# HK0J2071758B03-AM-FPC.net
KiCad netlist of a schematic drawn in Altium Designer
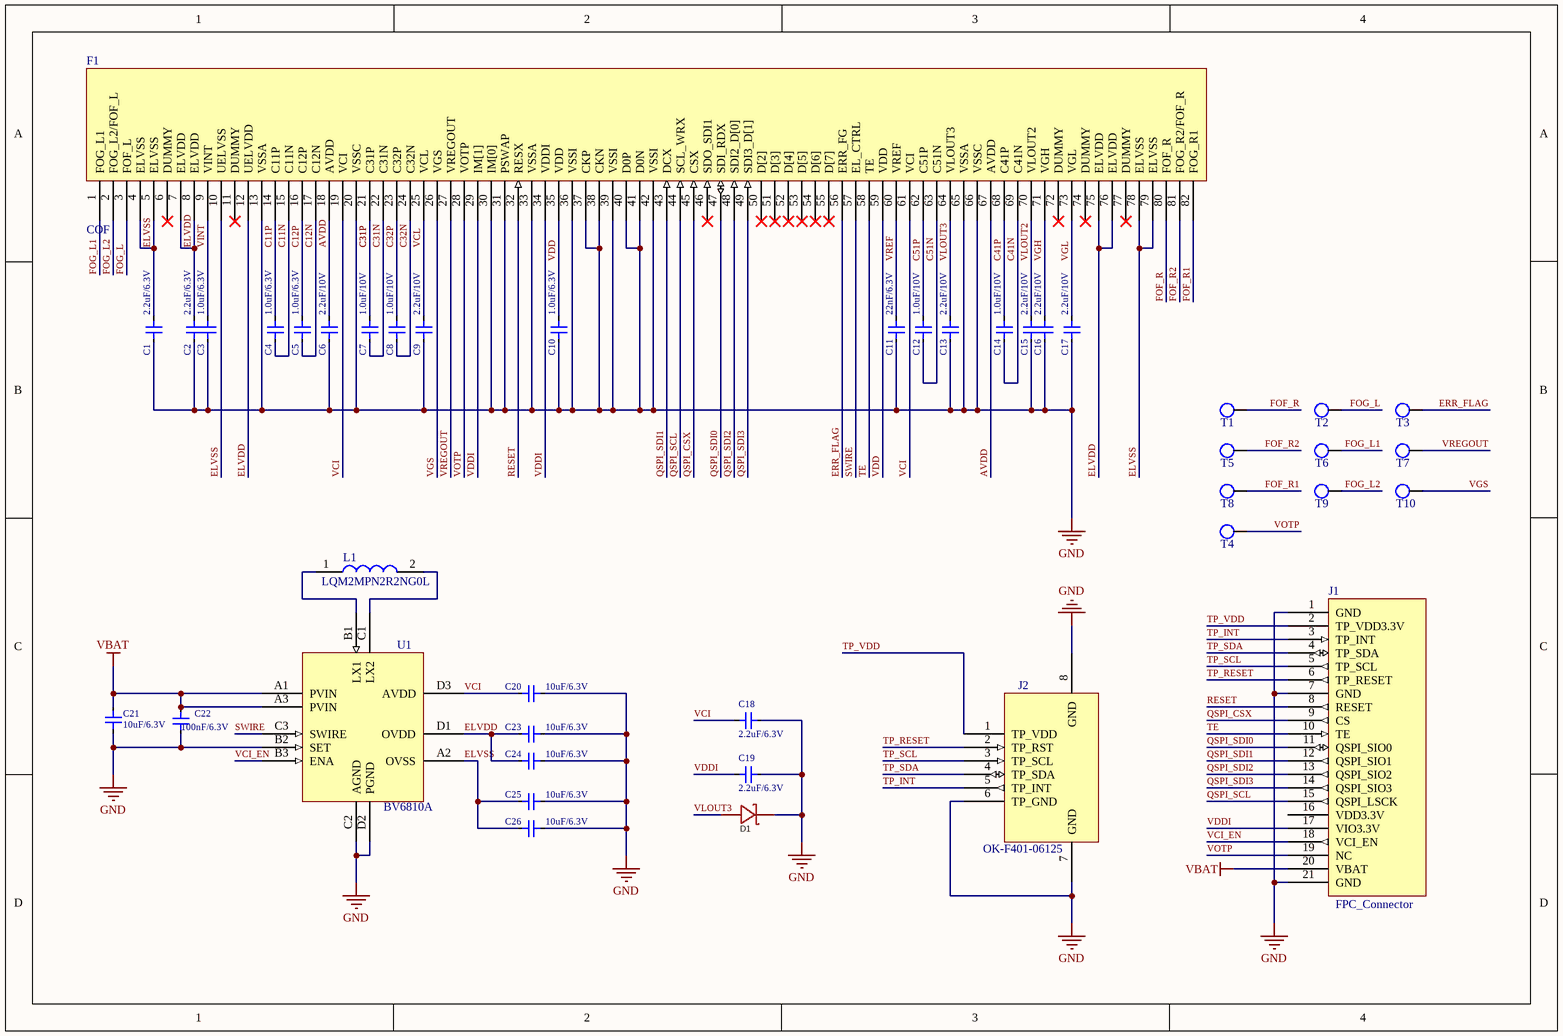
[diagram p0: HK0J2071758B03-AM-FPC.SchDoc]

(export (version "E")
  (design (tool "Eeschema 10.0.6"))
  (components
    (comp (ref "C1")
      (value "2.2uF/6.3V")
      (footprint "CAPC0603X33N")
      (description "NONE")
      (fields
        (field (name "MANUFACTURER") "Murata")
        (field (name "MANUFACTURER PART NUMBER") "GRM033R61A105ME15D")
      )
      (libsource (lib "COF") (part "Capacitor"))
    )
    (comp (ref "C2")
      (value "2.2uF/6.3V")
      (footprint "CAPC0603X33N")
      (description "NONE")
      (fields
        (field (name "MANUFACTURER") "Murata")
        (field (name "MANUFACTURER PART NUMBER") "GRM033R61A105ME15D")
      )
      (libsource (lib "COF") (part "Capacitor"))
    )
    (comp (ref "C3")
      (value "1.0uF/6.3V")
      (footprint "CAPC0603X33N")
      (description "NONE")
      (fields
        (field (name "MANUFACTURER") "Murata")
        (field (name "MANUFACTURER PART NUMBER") "GRM033R61A105ME15D")
      )
      (libsource (lib "COF") (part "Capacitor"))
    )
    (comp (ref "C4")
      (value "1.0uF/6.3V")
      (footprint "CAPC0603X33N")
      (description "NONE")
      (fields
        (field (name "MANUFACTURER") "Murata")
        (field (name "MANUFACTURER PART NUMBER") "GRM033R61A105ME15D")
      )
      (libsource (lib "COF") (part "Capacitor"))
    )
    (comp (ref "C5")
      (value "1.0uF/6.3V")
      (footprint "CAPC0603X33N")
      (description "NONE")
      (fields
        (field (name "MANUFACTURER") "Murata")
        (field (name "MANUFACTURER PART NUMBER") "GRM033R61A105ME15D")
      )
      (libsource (lib "COF") (part "Capacitor"))
    )
    (comp (ref "C6")
      (value "2.2uF/10V")
      (footprint "CAPC0603X33N")
      (description "NONE")
      (fields
        (field (name "MANUFACTURER") "Murata")
        (field (name "MANUFACTURER PART NUMBER") "GRM033R61A105ME15D")
      )
      (libsource (lib "COF") (part "Capacitor"))
    )
    (comp (ref "C7")
      (value "1.0uF/10V")
      (footprint "CAPC0603X33N")
      (description "NONE")
      (fields
        (field (name "MANUFACTURER") "Murata")
        (field (name "MANUFACTURER PART NUMBER") "GRM033R61A105ME15D")
      )
      (libsource (lib "COF") (part "Capacitor"))
    )
    (comp (ref "C8")
      (value "1.0uF/10V")
      (footprint "CAPC0603X33N")
      (description "NONE")
      (fields
        (field (name "MANUFACTURER") "Murata")
        (field (name "MANUFACTURER PART NUMBER") "GRM033R61A105ME15D")
      )
      (libsource (lib "COF") (part "Capacitor"))
    )
    (comp (ref "C9")
      (value "2.2uF/10V")
      (footprint "CAPC0603X33N")
      (description "NONE")
      (fields
        (field (name "MANUFACTURER") "Murata")
        (field (name "MANUFACTURER PART NUMBER") "GRM033R61A105ME15D")
      )
      (libsource (lib "COF") (part "Capacitor"))
    )
    (comp (ref "C10")
      (value "1.0uF/6.3V")
      (footprint "CAPC0603X33N")
      (description "NONE")
      (fields
        (field (name "MANUFACTURER") "Murata")
        (field (name "MANUFACTURER PART NUMBER") "GRM033R61A105ME15D")
      )
      (libsource (lib "COF") (part "Capacitor"))
    )
    (comp (ref "C11")
      (value "22nF/6.3V")
      (footprint "CAPC0603X33N")
      (description "NONE")
      (fields
        (field (name "MANUFACTURER") "Murata")
        (field (name "MANUFACTURER PART NUMBER") "GRM033R61A105ME15D")
      )
      (libsource (lib "COF") (part "Capacitor"))
    )
    (comp (ref "C12")
      (value "1.0uF/10V")
      (footprint "CAPC0603X33N")
      (description "NONE")
      (fields
        (field (name "MANUFACTURER") "Murata")
        (field (name "MANUFACTURER PART NUMBER") "GRM033R61A105ME15D")
      )
      (libsource (lib "COF") (part "Capacitor"))
    )
    (comp (ref "C13")
      (value "2.2uF/10V")
      (footprint "CAPC0603X33N")
      (description "NONE")
      (fields
        (field (name "MANUFACTURER") "Murata")
        (field (name "MANUFACTURER PART NUMBER") "GRM033R61A105ME15D")
      )
      (libsource (lib "COF") (part "Capacitor"))
    )
    (comp (ref "C14")
      (value "1.0uF/10V")
      (footprint "CAPC0603X33N")
      (description "NONE")
      (fields
        (field (name "MANUFACTURER") "Murata")
        (field (name "MANUFACTURER PART NUMBER") "GRM033R61A105ME15D")
      )
      (libsource (lib "COF") (part "Capacitor"))
    )
    (comp (ref "C15")
      (value "2.2uF/10V")
      (footprint "CAPC0603X33N")
      (description "NONE")
      (fields
        (field (name "MANUFACTURER") "Murata")
        (field (name "MANUFACTURER PART NUMBER") "GRM033R61A105ME15D")
      )
      (libsource (lib "COF") (part "Capacitor"))
    )
    (comp (ref "C16")
      (value "2.2uF/10V")
      (footprint "CAPC0603X33N")
      (description "NONE")
      (fields
        (field (name "MANUFACTURER") "Murata")
        (field (name "MANUFACTURER PART NUMBER") "GRM033R61A105ME15D")
      )
      (libsource (lib "COF") (part "Capacitor"))
    )
    (comp (ref "C17")
      (value "2.2uF/10V")
      (footprint "CAPC0603X33N")
      (description "NONE")
      (fields
        (field (name "MANUFACTURER") "Murata")
        (field (name "MANUFACTURER PART NUMBER") "GRM033R61A105ME15D")
      )
      (libsource (lib "COF") (part "Capacitor"))
    )
    (comp (ref "C18")
      (value "2.2uF/6.3V")
      (footprint "CAPC0603X33N")
      (description "NONE")
      (fields
        (field (name "MANUFACTURER") "Murata")
        (field (name "MANUFACTURER PART NUMBER") "GRM033R61A105ME15D")
      )
      (libsource (lib "COF") (part "Capacitor"))
    )
    (comp (ref "C19")
      (value "2.2uF/6.3V")
      (footprint "CAPC0603X33N")
      (description "NONE")
      (fields
        (field (name "MANUFACTURER") "Murata")
        (field (name "MANUFACTURER PART NUMBER") "GRM033R61A105ME15D")
      )
      (libsource (lib "COF") (part "Capacitor"))
    )
    (comp (ref "C20")
      (value "10uF/6.3V")
      (footprint "CAPC1005X57N")
      (description "NONE")
      (fields
        (field (name "MANUFACTURER") "Murata")
        (field (name "MANUFACTURER PART NUMBER") "GRM033R61A105ME15D")
      )
      (libsource (lib "COF") (part "Capacitor"))
    )
    (comp (ref "C21")
      (value "10uF/6.3V")
      (footprint "CAPC1005X57N")
      (description "NONE")
      (fields
        (field (name "MANUFACTURER") "Murata")
        (field (name "MANUFACTURER PART NUMBER") "GRM033R61A105ME15D")
      )
      (libsource (lib "COF") (part "Capacitor"))
    )
    (comp (ref "C22")
      (value "100nF/6.3V")
      (footprint "CAPC0603X33N")
      (description "NONE")
      (fields
        (field (name "MANUFACTURER") "Murata")
        (field (name "MANUFACTURER PART NUMBER") "GRM033R61A105ME15D")
      )
      (libsource (lib "COF") (part "Capacitor"))
    )
    (comp (ref "C23")
      (value "10uF/6.3V")
      (footprint "CAPC1005X57N")
      (description "NONE")
      (fields
        (field (name "MANUFACTURER") "Murata")
        (field (name "MANUFACTURER PART NUMBER") "GRM033R61A105ME15D")
      )
      (libsource (lib "COF") (part "Capacitor"))
    )
    (comp (ref "C24")
      (value "10uF/6.3V")
      (footprint "CAPC1005X57N")
      (description "NONE")
      (fields
        (field (name "MANUFACTURER") "Murata")
        (field (name "MANUFACTURER PART NUMBER") "GRM033R61A105ME15D")
      )
      (libsource (lib "COF") (part "Capacitor"))
    )
    (comp (ref "C25")
      (value "10uF/6.3V")
      (footprint "CAPC1005X57N")
      (description "NONE")
      (fields
        (field (name "MANUFACTURER") "Murata")
        (field (name "MANUFACTURER PART NUMBER") "GRM033R61A105ME15D")
      )
      (libsource (lib "COF") (part "Capacitor"))
    )
    (comp (ref "C26")
      (value "10uF/6.3V")
      (footprint "CAPC1005X57N")
      (description "NONE")
      (fields
        (field (name "MANUFACTURER") "Murata")
        (field (name "MANUFACTURER PART NUMBER") "GRM033R61A105ME15D")
      )
      (libsource (lib "COF") (part "Capacitor"))
    )
    (comp (ref "D1")
      (value "LDSR01S30ST5G")
      (footprint "DFN0603-D_L0.6-W0.3-P0.34-RD")
      (fields (field (name "MANUFACTURER") "LRC(乐山无线电)"))
      (libsource (lib "COF") (part "LDSR01S30ST5G"))
    )
    (comp (ref "F1") (value "COF") (footprint "COF Connector") (libsource (lib "COF") (part "COF")))
    (comp (ref "J1")
      (value "FPC_Connector")
      (footprint "FPC Connector")
      (libsource (lib "COF") (part "21Pin_Connector"))
    )
    (comp (ref "J2")
      (value "OK-F401-06125")
      (footprint "FFC-SMD_6P-P0.50_FH34SRJ-6S-0.5SH")
      (libsource (lib "COF") (part "OK-F401-06125"))
    )
    (comp (ref "L1")
      (value "LQM2MPN2R2NG0L")
      (footprint "LQM2MPN1R0NG0L")
      (description "Inductor")
      (fields (field (name "MOUSER PART NUMBER") "81-LQM2MPN2R2NG0L"))
      (libsource (lib "COF") (part "LQM2MPN2R2NG0L"))
    )
    (comp (ref "T1")
      (value "Test_Point")
      (footprint "TP-C045-PI")
      (libsource (lib "COF") (part "Test_Point"))
    )
    (comp (ref "T2")
      (value "Test_Point")
      (footprint "TP-C045-PI")
      (libsource (lib "COF") (part "Test_Point"))
    )
    (comp (ref "T3")
      (value "Test_Point")
      (footprint "TP-C045-PI")
      (libsource (lib "COF") (part "Test_Point"))
    )
    (comp (ref "T4")
      (value "Test_Point")
      (footprint "TP-C045-PI")
      (libsource (lib "COF") (part "Test_Point"))
    )
    (comp (ref "T5")
      (value "Test_Point")
      (footprint "TP-C045-PI")
      (libsource (lib "COF") (part "Test_Point"))
    )
    (comp (ref "T6")
      (value "Test_Point")
      (footprint "TP-C045-PI")
      (libsource (lib "COF") (part "Test_Point"))
    )
    (comp (ref "T7")
      (value "Test_Point")
      (footprint "TP-C045-PI")
      (libsource (lib "COF") (part "Test_Point"))
    )
    (comp (ref "T8")
      (value "Test_Point")
      (footprint "TP-C045-PI")
      (libsource (lib "COF") (part "Test_Point"))
    )
    (comp (ref "T9")
      (value "Test_Point")
      (footprint "TP-C045-PI")
      (libsource (lib "COF") (part "Test_Point"))
    )
    (comp (ref "T10")
      (value "Test_Point")
      (footprint "TP-C045-PI")
      (libsource (lib "COF") (part "Test_Point"))
    )
    (comp (ref "U1")
      (value "BV6810A")
      (footprint "WLCSP-12_L1.7-W1.5-R4-C3-P0.40-TL-1")
      (libsource (lib "COF") (part "BV6810A"))
    )
  )
  (nets
    (net (code "1") (name "/AVDD") (class "Default")
      (node (ref "C6") (pin "1") (pinfunction "1_1") (pintype "passive"))
      (node (ref "F1") (pin "18") (pinfunction "AVDD_18") (pintype "power_in"))
      (node (ref "F1") (pin "67") (pinfunction "AVDD_67") (pintype "power_in"))
    )
    (net (code "2") (name "/C11N") (class "Default")
      (node (ref "C4") (pin "2") (pinfunction "2_2") (pintype "passive"))
      (node (ref "F1") (pin "15") (pinfunction "C11N_15") (pintype "tri_state"))
    )
    (net (code "3") (name "/C11P") (class "Default")
      (node (ref "C4") (pin "1") (pinfunction "1_1") (pintype "passive"))
      (node (ref "F1") (pin "14") (pinfunction "C11P_14") (pintype "tri_state"))
    )
    (net (code "4") (name "/C12N") (class "Default")
      (node (ref "C5") (pin "2") (pinfunction "2_2") (pintype "passive"))
      (node (ref "F1") (pin "17") (pinfunction "C12N_17") (pintype "tri_state"))
    )
    (net (code "5") (name "/C12P") (class "Default")
      (node (ref "C5") (pin "1") (pinfunction "1_1") (pintype "passive"))
      (node (ref "F1") (pin "16") (pinfunction "C12P_16") (pintype "tri_state"))
    )
    (net (code "6") (name "/C31N") (class "Default")
      (node (ref "C7") (pin "2") (pinfunction "2_2") (pintype "passive"))
      (node (ref "F1") (pin "22") (pinfunction "C31N_22") (pintype "tri_state"))
    )
    (net (code "7") (name "/C31P") (class "Default")
      (node (ref "C7") (pin "1") (pinfunction "1_1") (pintype "passive"))
      (node (ref "F1") (pin "21") (pinfunction "C31P_21") (pintype "tri_state"))
    )
    (net (code "8") (name "/C32N") (class "Default")
      (node (ref "C8") (pin "2") (pinfunction "2_2") (pintype "passive"))
      (node (ref "F1") (pin "24") (pinfunction "C32N_24") (pintype "tri_state"))
    )
    (net (code "9") (name "/C32P") (class "Default")
      (node (ref "C8") (pin "1") (pinfunction "1_1") (pintype "passive"))
      (node (ref "F1") (pin "23") (pinfunction "C32P_23") (pintype "tri_state"))
    )
    (net (code "10") (name "/C41N") (class "Default")
      (node (ref "C14") (pin "2") (pinfunction "2_2") (pintype "passive"))
      (node (ref "F1") (pin "69") (pinfunction "C41N_69") (pintype "tri_state"))
    )
    (net (code "11") (name "/C41P") (class "Default")
      (node (ref "C14") (pin "1") (pinfunction "1_1") (pintype "passive"))
      (node (ref "F1") (pin "68") (pinfunction "C41P_68") (pintype "tri_state"))
    )
    (net (code "12") (name "/C51N") (class "Default")
      (node (ref "C12") (pin "2") (pinfunction "2_2") (pintype "passive"))
      (node (ref "F1") (pin "63") (pinfunction "C51N_63") (pintype "tri_state"))
    )
    (net (code "13") (name "/C51P") (class "Default")
      (node (ref "C12") (pin "1") (pinfunction "1_1") (pintype "passive"))
      (node (ref "F1") (pin "62") (pinfunction "C51P_62") (pintype "tri_state"))
    )
    (net (code "14") (name "/ELVDD") (class "Default")
      (node (ref "C2") (pin "1") (pinfunction "1_1") (pintype "passive"))
      (node (ref "C23") (pin "2") (pinfunction "2_2") (pintype "passive"))
      (node (ref "C24") (pin "2") (pinfunction "2_2") (pintype "passive"))
      (node (ref "F1") (pin "12") (pinfunction "UELVDD_12") (pintype "power_in"))
      (node (ref "F1") (pin "7") (pinfunction "ELVDD_7") (pintype "power_in"))
      (node (ref "F1") (pin "75") (pinfunction "ELVDD_75") (pintype "power_in"))
      (node (ref "F1") (pin "76") (pinfunction "ELVDD_76") (pintype "power_in"))
      (node (ref "F1") (pin "8") (pinfunction "ELVDD_8") (pintype "power_in"))
      (node (ref "U1") (pin "D1") (pinfunction "OVDD_D1") (pintype "power_in"))
    )
    (net (code "15") (name "/ELVSS") (class "Default")
      (node (ref "C1") (pin "1") (pinfunction "1_1") (pintype "passive"))
      (node (ref "C25") (pin "2") (pinfunction "2_2") (pintype "passive"))
      (node (ref "C26") (pin "2") (pinfunction "2_2") (pintype "passive"))
      (node (ref "F1") (pin "10") (pinfunction "UELVSS_10") (pintype "power_in"))
      (node (ref "F1") (pin "4") (pinfunction "ELVSS_4") (pintype "power_in"))
      (node (ref "F1") (pin "5") (pinfunction "ELVSS_5") (pintype "power_in"))
      (node (ref "F1") (pin "78") (pinfunction "ELVSS_78") (pintype "power_in"))
      (node (ref "F1") (pin "79") (pinfunction "ELVSS_79") (pintype "power_in"))
      (node (ref "U1") (pin "A2") (pinfunction "OVSS_A2") (pintype "power_in"))
    )
    (net (code "16") (name "/ERR_FLAG") (class "Default")
      (node (ref "F1") (pin "56") (pinfunction "ERR_FG_56") (pintype "tri_state"))
      (node (ref "T3") (pin "1") (pinfunction "1_1") (pintype "passive"))
    )
    (net (code "17") (name "/FOF_R") (class "Default")
      (node (ref "F1") (pin "80") (pinfunction "FOF_R_80") (pintype "tri_state"))
      (node (ref "T1") (pin "1") (pinfunction "1_1") (pintype "passive"))
    )
    (net (code "18") (name "/FOF_R1") (class "Default")
      (node (ref "F1") (pin "82") (pinfunction "FOG_R1_82") (pintype "tri_state"))
      (node (ref "T8") (pin "1") (pinfunction "1_1") (pintype "passive"))
    )
    (net (code "19") (name "/FOF_R2") (class "Default")
      (node (ref "F1") (pin "81") (pinfunction "FOG_R2/FOF_R_81") (pintype "tri_state"))
      (node (ref "T5") (pin "1") (pinfunction "1_1") (pintype "passive"))
    )
    (net (code "20") (name "/FOG_L") (class "Default")
      (node (ref "F1") (pin "3") (pinfunction "FOF_L_3") (pintype "tri_state"))
      (node (ref "T2") (pin "1") (pinfunction "1_1") (pintype "passive"))
    )
    (net (code "21") (name "/FOG_L1") (class "Default")
      (node (ref "F1") (pin "1") (pinfunction "FOG_L1_1") (pintype "tri_state"))
      (node (ref "T6") (pin "1") (pinfunction "1_1") (pintype "passive"))
    )
    (net (code "22") (name "/FOG_L2") (class "Default")
      (node (ref "F1") (pin "2") (pinfunction "FOG_L2/FOF_L_2") (pintype "tri_state"))
      (node (ref "T9") (pin "1") (pinfunction "1_1") (pintype "passive"))
    )
    (net (code "23") (name "/QSPI_CSX") (class "Default")
      (node (ref "F1") (pin "45") (pinfunction "CSX_45") (pintype "input"))
      (node (ref "J1") (pin "9") (pinfunction "CS_9") (pintype "output"))
    )
    (net (code "24") (name "/QSPI_SCL") (class "Default")
      (node (ref "F1") (pin "44") (pinfunction "SCL_WRX_44") (pintype "input"))
      (node (ref "J1") (pin "15") (pinfunction "QSPI_LSCK_15") (pintype "output"))
    )
    (net (code "25") (name "/QSPI_SDI0") (class "Default")
      (node (ref "F1") (pin "47") (pinfunction "SDI_RDX_47") (pintype "bidirectional"))
      (node (ref "J1") (pin "11") (pinfunction "QSPI_SIO0_11") (pintype "bidirectional"))
    )
    (net (code "26") (name "/QSPI_SDI1") (class "Default")
      (node (ref "F1") (pin "43") (pinfunction "DCX_43") (pintype "input"))
      (node (ref "J1") (pin "12") (pinfunction "QSPI_SIO1_12") (pintype "output"))
    )
    (net (code "27") (name "/QSPI_SDI2") (class "Default")
      (node (ref "F1") (pin "48") (pinfunction "SDI2_D[0]_48") (pintype "input"))
      (node (ref "J1") (pin "13") (pinfunction "QSPI_SIO2_13") (pintype "output"))
    )
    (net (code "28") (name "/QSPI_SDI3") (class "Default")
      (node (ref "F1") (pin "49") (pinfunction "SDI3_D[1]_49") (pintype "input"))
      (node (ref "J1") (pin "14") (pinfunction "QSPI_SIO3_14") (pintype "output"))
    )
    (net (code "29") (name "/RESET") (class "Default")
      (node (ref "F1") (pin "32") (pinfunction "RESX_32") (pintype "input"))
      (node (ref "J1") (pin "8") (pinfunction "RESET_8") (pintype "output"))
    )
    (net (code "30") (name "/SWIRE") (class "Default")
      (node (ref "F1") (pin "57") (pinfunction "EL_CTRL_57") (pintype "tri_state"))
      (node (ref "U1") (pin "C3") (pinfunction "SWIRE_C3") (pintype "input"))
    )
    (net (code "31") (name "/TE") (class "Default")
      (node (ref "F1") (pin "58") (pinfunction "TE_58") (pintype "tri_state"))
      (node (ref "J1") (pin "10") (pinfunction "TE_10") (pintype "input"))
    )
    (net (code "32") (name "/TP_INT") (class "Default")
      (node (ref "J1") (pin "3") (pinfunction "TP_INT_3") (pintype "input"))
      (node (ref "J2") (pin "5") (pinfunction "TP_INT_5") (pintype "output"))
    )
    (net (code "33") (name "/TP_RESET") (class "Default")
      (node (ref "J1") (pin "6") (pinfunction "TP_RESET_6") (pintype "output"))
      (node (ref "J2") (pin "2") (pinfunction "TP_RST_2") (pintype "input"))
    )
    (net (code "34") (name "/TP_SCL") (class "Default")
      (node (ref "J1") (pin "5") (pinfunction "TP_SCL_5") (pintype "output"))
      (node (ref "J2") (pin "3") (pinfunction "TP_SCL_3") (pintype "input"))
    )
    (net (code "35") (name "/TP_SDA") (class "Default")
      (node (ref "J1") (pin "4") (pinfunction "TP_SDA_4") (pintype "bidirectional"))
      (node (ref "J2") (pin "4") (pinfunction "TP_SDA_4") (pintype "bidirectional"))
    )
    (net (code "36") (name "/TP_VDD") (class "Default")
      (node (ref "J1") (pin "2") (pinfunction "TP_VDD3.3V_2") (pintype "power_in"))
      (node (ref "J2") (pin "1") (pinfunction "TP_VDD_1") (pintype "power_in"))
    )
    (net (code "37") (name "/VCI") (class "Default")
      (node (ref "C18") (pin "1") (pinfunction "1_1") (pintype "passive"))
      (node (ref "C20") (pin "2") (pinfunction "2_2") (pintype "passive"))
      (node (ref "F1") (pin "19") (pinfunction "VCI_19") (pintype "power_in"))
      (node (ref "F1") (pin "61") (pinfunction "VCI_61") (pintype "power_in"))
      (node (ref "U1") (pin "D3") (pinfunction "AVDD_D3") (pintype "power_in"))
    )
    (net (code "38") (name "/VCI_EN") (class "Default")
      (node (ref "J1") (pin "18") (pinfunction "VCI_EN_18") (pintype "output"))
      (node (ref "U1") (pin "B3") (pinfunction "ENA_B3") (pintype "input"))
    )
    (net (code "39") (name "/VCL") (class "Default")
      (node (ref "C9") (pin "1") (pinfunction "1_1") (pintype "passive"))
      (node (ref "F1") (pin "25") (pinfunction "VCL_25") (pintype "power_in"))
    )
    (net (code "40") (name "/VDD") (class "Default")
      (node (ref "C10") (pin "1") (pinfunction "1_1") (pintype "passive"))
      (node (ref "F1") (pin "35") (pinfunction "VDD_35") (pintype "power_in"))
      (node (ref "F1") (pin "59") (pinfunction "VDD_59") (pintype "power_in"))
    )
    (net (code "41") (name "/VDDI") (class "Default")
      (node (ref "C19") (pin "1") (pinfunction "1_1") (pintype "passive"))
      (node (ref "F1") (pin "29") (pinfunction "IM[1]_29") (pintype "passive"))
      (node (ref "F1") (pin "34") (pinfunction "VDDI_34") (pintype "power_in"))
      (node (ref "J1") (pin "17") (pinfunction "VIO3.3V_17") (pintype "power_in"))
    )
    (net (code "42") (name "/VGH") (class "Default")
      (node (ref "C16") (pin "1") (pinfunction "1_1") (pintype "passive"))
      (node (ref "F1") (pin "71") (pinfunction "VGH_71") (pintype "tri_state"))
    )
    (net (code "43") (name "/VGL") (class "Default")
      (node (ref "C17") (pin "1") (pinfunction "1_1") (pintype "passive"))
      (node (ref "F1") (pin "73") (pinfunction "VGL_73") (pintype "power_in"))
    )
    (net (code "44") (name "/VGS") (class "Default")
      (node (ref "F1") (pin "26") (pinfunction "VGS_26") (pintype "power_in"))
      (node (ref "T10") (pin "1") (pinfunction "1_1") (pintype "passive"))
    )
    (net (code "45") (name "/VINT") (class "Default")
      (node (ref "C3") (pin "1") (pinfunction "1_1") (pintype "passive"))
      (node (ref "F1") (pin "9") (pinfunction "VINT_9") (pintype "tri_state"))
    )
    (net (code "46") (name "/VLOUT2") (class "Default")
      (node (ref "C15") (pin "1") (pinfunction "1_1") (pintype "passive"))
      (node (ref "F1") (pin "70") (pinfunction "VLOUT2_70") (pintype "power_in"))
    )
    (net (code "47") (name "/VLOUT3") (class "Default")
      (node (ref "C13") (pin "1") (pinfunction "1_1") (pintype "passive"))
      (node (ref "D1") (pin "2") (pinfunction "A_2") (pintype "passive"))
      (node (ref "F1") (pin "64") (pinfunction "VLOUT3_64") (pintype "power_in"))
    )
    (net (code "48") (name "/VOTP") (class "Default")
      (node (ref "F1") (pin "28") (pinfunction "VOTP_28") (pintype "power_in"))
      (node (ref "J1") (pin "19") (pinfunction "NC_19") (pintype "passive"))
      (node (ref "T4") (pin "1") (pinfunction "1_1") (pintype "passive"))
    )
    (net (code "49") (name "/VREF") (class "Default")
      (node (ref "C11") (pin "1") (pinfunction "1_1") (pintype "passive"))
      (node (ref "F1") (pin "60") (pinfunction "VREF_60") (pintype "power_in"))
    )
    (net (code "50") (name "/VREGOUT") (class "Default")
      (node (ref "F1") (pin "27") (pinfunction "VREGOUT_27") (pintype "power_in"))
      (node (ref "T7") (pin "1") (pinfunction "1_1") (pintype "passive"))
    )
    (net (code "51") (name "GND") (class "Default")
      (node (ref "C1") (pin "2") (pinfunction "2_2") (pintype "passive"))
      (node (ref "C10") (pin "2") (pinfunction "2_2") (pintype "passive"))
      (node (ref "C11") (pin "2") (pinfunction "2_2") (pintype "passive"))
      (node (ref "C13") (pin "2") (pinfunction "2_2") (pintype "passive"))
      (node (ref "C15") (pin "2") (pinfunction "2_2") (pintype "passive"))
      (node (ref "C16") (pin "2") (pinfunction "2_2") (pintype "passive"))
      (node (ref "C17") (pin "2") (pinfunction "2_2") (pintype "passive"))
      (node (ref "C18") (pin "2") (pinfunction "2_2") (pintype "passive"))
      (node (ref "C19") (pin "2") (pinfunction "2_2") (pintype "passive"))
      (node (ref "C2") (pin "2") (pinfunction "2_2") (pintype "passive"))
      (node (ref "C20") (pin "1") (pinfunction "1_1") (pintype "passive"))
      (node (ref "C21") (pin "1") (pinfunction "1_1") (pintype "passive"))
      (node (ref "C22") (pin "2") (pinfunction "2_2") (pintype "passive"))
      (node (ref "C23") (pin "1") (pinfunction "1_1") (pintype "passive"))
      (node (ref "C24") (pin "1") (pinfunction "1_1") (pintype "passive"))
      (node (ref "C25") (pin "1") (pinfunction "1_1") (pintype "passive"))
      (node (ref "C26") (pin "1") (pinfunction "1_1") (pintype "passive"))
      (node (ref "C3") (pin "2") (pinfunction "2_2") (pintype "passive"))
      (node (ref "C6") (pin "2") (pinfunction "2_2") (pintype "passive"))
      (node (ref "C9") (pin "2") (pinfunction "2_2") (pintype "passive"))
      (node (ref "D1") (pin "1") (pinfunction "C_1") (pintype "passive"))
      (node (ref "F1") (pin "13") (pinfunction "VSSA_13") (pintype "power_in"))
      (node (ref "F1") (pin "20") (pinfunction "VSSC_20") (pintype "power_in"))
      (node (ref "F1") (pin "30") (pinfunction "IM[0]_30") (pintype "passive"))
      (node (ref "F1") (pin "31") (pinfunction "PSWAP_31") (pintype "passive"))
      (node (ref "F1") (pin "33") (pinfunction "VSSA_33") (pintype "power_in"))
      (node (ref "F1") (pin "36") (pinfunction "VSSI_36") (pintype "power_in"))
      (node (ref "F1") (pin "37") (pinfunction "CKP_37") (pintype "passive"))
      (node (ref "F1") (pin "38") (pinfunction "CKN_38") (pintype "passive"))
      (node (ref "F1") (pin "39") (pinfunction "VSSI_39") (pintype "power_in"))
      (node (ref "F1") (pin "40") (pinfunction "D0P_40") (pintype "passive"))
      (node (ref "F1") (pin "41") (pinfunction "D0N_41") (pintype "passive"))
      (node (ref "F1") (pin "42") (pinfunction "VSSI_42") (pintype "power_in"))
      (node (ref "F1") (pin "65") (pinfunction "VSSA_65") (pintype "power_in"))
      (node (ref "F1") (pin "66") (pinfunction "VSSC_66") (pintype "power_in"))
      (node (ref "J1") (pin "1") (pinfunction "GND_1") (pintype "power_in"))
      (node (ref "J1") (pin "21") (pinfunction "GND_21") (pintype "power_in"))
      (node (ref "J1") (pin "7") (pinfunction "GND_7") (pintype "power_in"))
      (node (ref "J2") (pin "6") (pinfunction "TP_GND_6") (pintype "power_in"))
      (node (ref "J2") (pin "7") (pinfunction "GND_7") (pintype "power_in"))
      (node (ref "J2") (pin "8") (pinfunction "GND_8") (pintype "power_in"))
      (node (ref "U1") (pin "B2") (pinfunction "SET_B2") (pintype "input"))
      (node (ref "U1") (pin "C2") (pinfunction "AGND_C2") (pintype "power_in"))
      (node (ref "U1") (pin "D2") (pinfunction "PGND_D2") (pintype "power_in"))
    )
    (net (code "52") (name "Net-(U1-LX1)") (class "Default")
      (node (ref "L1") (pin "1") (pinfunction "1_1") (pintype "passive"))
      (node (ref "U1") (pin "B1") (pinfunction "LX1_B1") (pintype "input"))
    )
    (net (code "53") (name "Net-(U1-LX2)") (class "Default")
      (node (ref "L1") (pin "2") (pinfunction "2_2") (pintype "passive"))
      (node (ref "U1") (pin "C1") (pinfunction "LX2_C1") (pintype "tri_state"))
    )
    (net (code "54") (name "VBAT") (class "Default")
      (node (ref "C21") (pin "2") (pinfunction "2_2") (pintype "passive"))
      (node (ref "C22") (pin "1") (pinfunction "1_1") (pintype "passive"))
      (node (ref "J1") (pin "20") (pinfunction "VBAT_20") (pintype "power_in"))
      (node (ref "U1") (pin "A1") (pinfunction "PVIN_A1") (pintype "power_in"))
      (node (ref "U1") (pin "A3") (pinfunction "PVIN_A3") (pintype "power_in"))
    )
    (net (code "55") (name "unconnected-(F1-DUMMY-Pad6)") (class "Default")
      (node (ref "F1") (pin "6") (pinfunction "DUMMY_6") (pintype "tri_state+no_connect"))
    )
    (net (code "56") (name "unconnected-(F1-DUMMY-Pad11)") (class "Default")
      (node (ref "F1") (pin "11") (pinfunction "DUMMY_11") (pintype "tri_state+no_connect"))
    )
    (net (code "57") (name "unconnected-(F1-DUMMY-Pad72)") (class "Default")
      (node (ref "F1") (pin "72") (pinfunction "DUMMY_72") (pintype "tri_state+no_connect"))
    )
    (net (code "58") (name "unconnected-(F1-DUMMY-Pad74)") (class "Default")
      (node (ref "F1") (pin "74") (pinfunction "DUMMY_74") (pintype "tri_state+no_connect"))
    )
    (net (code "59") (name "unconnected-(F1-DUMMY-Pad77)") (class "Default")
      (node (ref "F1") (pin "77") (pinfunction "DUMMY_77") (pintype "tri_state+no_connect"))
    )
    (net (code "60") (name "unconnected-(F1-D[2]-Pad50)") (class "Default")
      (node (ref "F1") (pin "50") (pinfunction "D[2]_50") (pintype "tri_state+no_connect"))
    )
    (net (code "61") (name "unconnected-(F1-D[3]-Pad51)") (class "Default")
      (node (ref "F1") (pin "51") (pinfunction "D[3]_51") (pintype "tri_state+no_connect"))
    )
    (net (code "62") (name "unconnected-(F1-D[4]-Pad52)") (class "Default")
      (node (ref "F1") (pin "52") (pinfunction "D[4]_52") (pintype "tri_state+no_connect"))
    )
    (net (code "63") (name "unconnected-(F1-D[5]-Pad53)") (class "Default")
      (node (ref "F1") (pin "53") (pinfunction "D[5]_53") (pintype "tri_state+no_connect"))
    )
    (net (code "64") (name "unconnected-(F1-D[6]-Pad54)") (class "Default")
      (node (ref "F1") (pin "54") (pinfunction "D[6]_54") (pintype "tri_state+no_connect"))
    )
    (net (code "65") (name "unconnected-(F1-D[7]-Pad55)") (class "Default")
      (node (ref "F1") (pin "55") (pinfunction "D[7]_55") (pintype "tri_state+no_connect"))
    )
    (net (code "66") (name "unconnected-(F1-SDO_SDI1-Pad46)") (class "Default")
      (node (ref "F1") (pin "46") (pinfunction "SDO_SDI1_46") (pintype "input+no_connect"))
    )
    (net (code "67") (name "unconnected-(J1-VDD3.3V-Pad16)") (class "Default")
      (node (ref "J1") (pin "16") (pinfunction "VDD3.3V_16") (pintype "power_in"))
    )
  )
)
